# ST_LINK_V2-1.net
KiCad netlist of a schematic drawn in Altium Designer
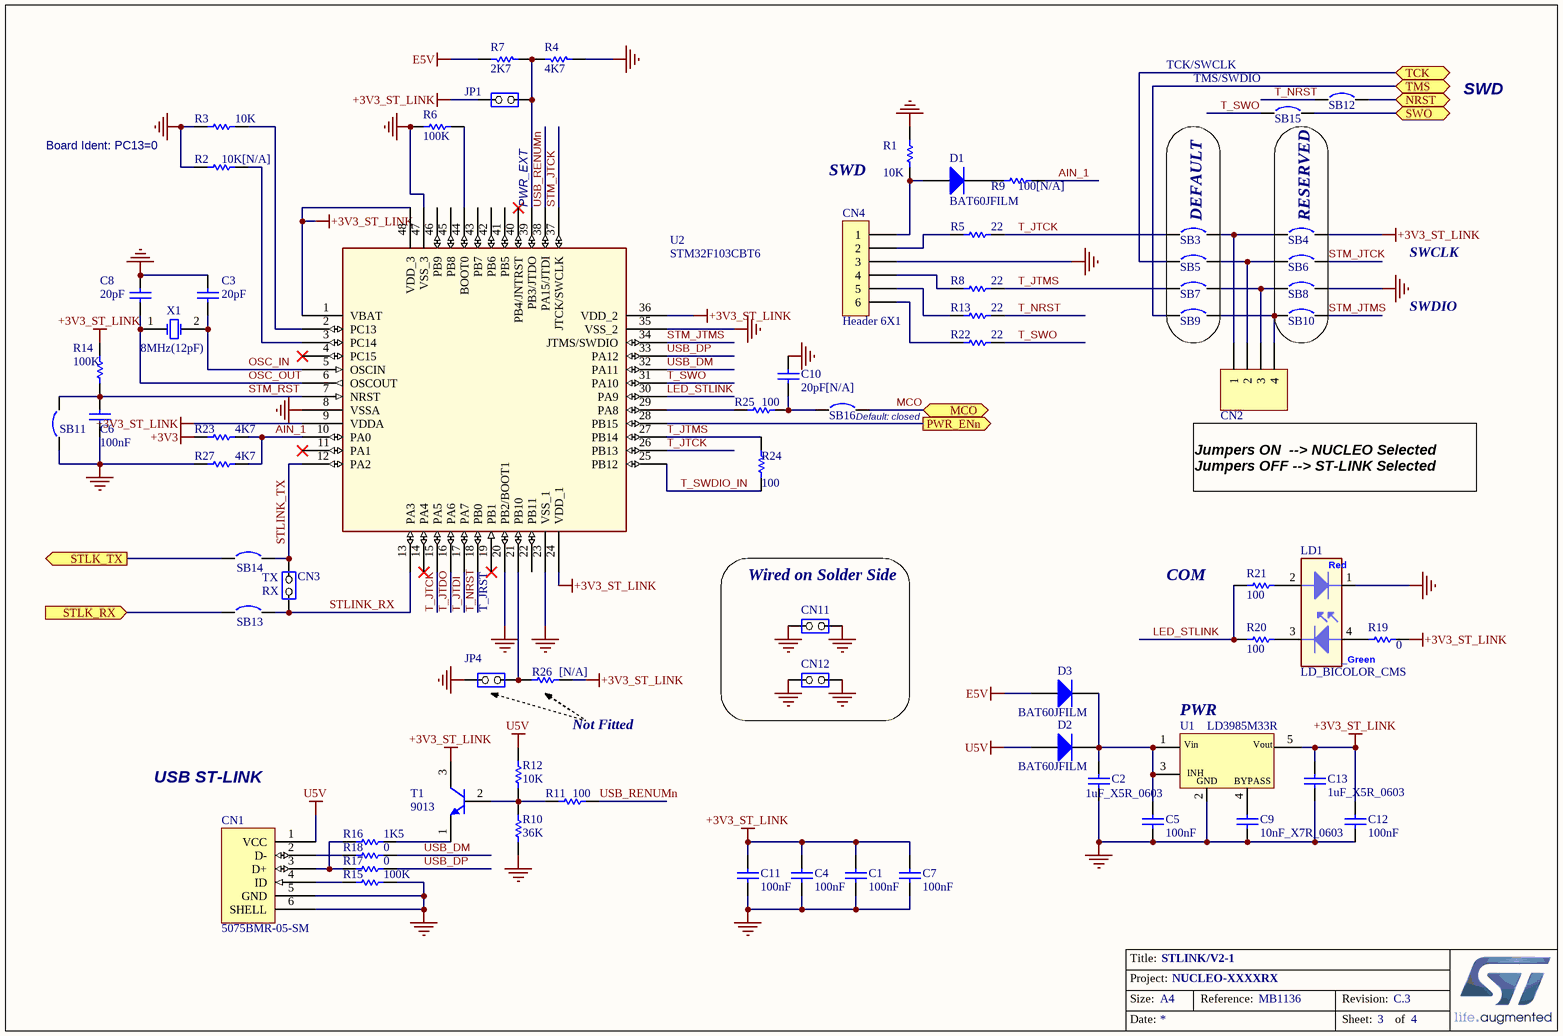
[diagram p0: ST_LINK_V2-1.SCHDOC]

(export (version "E")
  (design (tool "Eeschema 10.0.6"))
  (components
    (comp (ref "C1")
      (value "100nF")
      (footprint "0603C")
      (description "Capacitor 0402 / 0603 / 0805")
      (libsource (lib "MCD_TOOLS") (part "Capacitor_ST"))
    )
    (comp (ref "C2")
      (value "1uF_X5R_0603")
      (footprint "0603C")
      (description "0603  X5R 1µF")
      (fields (field (name "TOLERANCE") "10%"))
      (libsource (lib "MB963_1") (part "CAP SMD 0603  X5R 1µF 25V 10%"))
    )
    (comp (ref "C3")
      (value "20pF")
      (footprint "0603C")
      (description "Capacitor 0402 / 0603 / 0805")
      (libsource (lib "MCD_TOOLS") (part "Capacitor_ST"))
    )
    (comp (ref "C4")
      (value "100nF")
      (footprint "0603C")
      (description "Capacitor 0402 / 0603 / 0805")
      (libsource (lib "MCD_TOOLS") (part "Capacitor_ST"))
    )
    (comp (ref "C5")
      (value "100nF")
      (footprint "0603C")
      (description "Capacitor 0402 / 0603 / 0805")
      (libsource (lib "MCD_TOOLS") (part "Capacitor_ST"))
    )
    (comp (ref "C6")
      (value "100nF")
      (footprint "0603C")
      (description "Capacitor 0402 / 0603 / 0805")
      (libsource (lib "MCD_TOOLS") (part "Capacitor_ST"))
    )
    (comp (ref "C7")
      (value "100nF")
      (footprint "0603C")
      (description "Capacitor 0402 / 0603 / 0805")
      (libsource (lib "MCD_TOOLS") (part "Capacitor_ST"))
    )
    (comp (ref "C8")
      (value "20pF")
      (footprint "0603C")
      (description "Capacitor 0402 / 0603 / 0805")
      (libsource (lib "MCD_TOOLS") (part "Capacitor_ST"))
    )
    (comp (ref "C9")
      (value "10nF_X7R_0603")
      (footprint "0603C")
      (description "0603  X7R 10NF")
      (fields (field (name "TOLERANCE") "10%"))
      (libsource (lib "MB963_1") (part "CAP SMD 0603  X7R 10000PF 50V 10%"))
    )
    (comp (ref "C10")
      (value "20pF[N/A]")
      (footprint "0603C")
      (description "Capacitor 0402 / 0603 / 0805")
      (libsource (lib "MCD_TOOLS") (part "Capacitor_ST"))
    )
    (comp (ref "C11")
      (value "100nF")
      (footprint "0603C")
      (description "Capacitor 0402 / 0603 / 0805")
      (libsource (lib "MCD_TOOLS") (part "Capacitor_ST"))
    )
    (comp (ref "C12")
      (value "100nF")
      (footprint "0603C")
      (description "Capacitor 0402 / 0603 / 0805")
      (libsource (lib "MCD_TOOLS") (part "Capacitor_ST"))
    )
    (comp (ref "C13")
      (value "1uF_X5R_0603")
      (footprint "0603C")
      (description "0603  X5R 1µF")
      (fields (field (name "TOLERANCE") "10%"))
      (libsource (lib "MB963_1") (part "CAP SMD 0603  X5R 1µF 25V 10%"))
    )
    (comp (ref "CN1")
      (value "5075BMR-05-SM")
      (footprint "USB-MINI-B-SMD")
      (description "USB-MINI-typeB connector")
      (libsource (lib "MCD_TOOLS") (part "USB-MINI-typeB connector"))
    )
    (comp (ref "CN2")
      (value "Header 4")
      (footprint "1*4")
      (description "Header, 4-Pin, Single row")
      (fields (field (name "PUBLISHER") "Altium Limited"))
      (libsource (lib "Nucleo_64") (part "Header 4"))
    )
    (comp (ref "CN3") (value "~") (footprint "SIP2/2.54") (libsource (lib "MCD_TOOLS") (part "JP2")))
    (comp (ref "CN4")
      (value "Header 6X1")
      (footprint "1*6P")
      (description "Header, 6-Pin, Single row")
      (fields (field (name "PUBLISHER") "Altium Limited"))
      (libsource (lib "Nucleo_64") (part "Header 6X1"))
    )
    (comp (ref "CN11") (value "~") (footprint "SIP2/2.54") (libsource (lib "*") (part "JP2")))
    (comp (ref "CN12") (value "~") (footprint "SIP2/2.54") (libsource (lib "*") (part "JP2")))
    (comp (ref "D1")
      (value "BAT60JFILM")
      (footprint "SOD323/A")
      (libsource (lib "MCD_TOOLS") (part "BAT60JFILM"))
    )
    (comp (ref "D2")
      (value "BAT60JFILM")
      (footprint "SOD323/A")
      (libsource (lib "MCD_TOOLS") (part "BAT60JFILM"))
    )
    (comp (ref "D3")
      (value "BAT60JFILM")
      (footprint "SOD323/A")
      (libsource (lib "MCD_TOOLS") (part "BAT60JFILM"))
    )
    (comp (ref "JP1") (value "~") (footprint "SIP2/2.54") (libsource (lib "*") (part "JP2")))
    (comp (ref "JP4") (value "~") (footprint "SIP2/2.54") (libsource (lib "*") (part "JP2")))
    (comp (ref "LD1")
      (value "LD_BICOLOR_CMS")
      (footprint "HSMF-A201")
      (description "Bicolor Led")
      (libsource (lib "MCD_TOOLS") (part "LD_BICOLOR_CMS"))
    )
    (comp (ref "R1")
      (value "10K")
      (footprint "0603R")
      (description "Resistor 0402 or 0603 or 0805")
      (libsource (lib "Miscellaneous Devices") (part "Res1"))
    )
    (comp (ref "R2")
      (value "10K[N/A]")
      (footprint "0603R")
      (description "Resistor 0402 or 0603 or 0805")
      (libsource (lib "Miscellaneous Devices") (part "Res1"))
    )
    (comp (ref "R3")
      (value "10K")
      (footprint "0603R")
      (description "Resistor 0402 or 0603 or 0805")
      (libsource (lib "Miscellaneous Devices") (part "Res1"))
    )
    (comp (ref "R4")
      (value "4K7")
      (footprint "0603R")
      (description "Resistor")
      (fields (field (name "PUBLISHER") "Altium Limited"))
      (libsource (lib "") (part "Res1_2"))
    )
    (comp (ref "R5")
      (value "22")
      (footprint "0603R")
      (description "Resistor 0402 or 0603 or 0805")
      (libsource (lib "Miscellaneous Devices") (part "Res1"))
    )
    (comp (ref "R6")
      (value "100K")
      (footprint "0603R")
      (description "Resistor 0402 or 0603 or 0805")
      (libsource (lib "Miscellaneous Devices") (part "Res1"))
    )
    (comp (ref "R7")
      (value "2K7")
      (footprint "0603R")
      (description "Resistor")
      (fields (field (name "PUBLISHER") "Altium Limited"))
      (libsource (lib "") (part "Res1_2"))
    )
    (comp (ref "R8")
      (value "22")
      (footprint "0603R")
      (description "Resistor 0402 or 0603 or 0805")
      (libsource (lib "Miscellaneous Devices") (part "Res1"))
    )
    (comp (ref "R9")
      (value "100[N/A]")
      (footprint "0603R")
      (description "Resistor 0402 or 0603 or 0805")
      (libsource (lib "Miscellaneous Devices") (part "Res1"))
    )
    (comp (ref "R10")
      (value "36K")
      (footprint "0603R")
      (description "Resistor")
      (fields (field (name "PUBLISHER") "Altium Limited"))
      (libsource (lib "") (part "Res1_1"))
    )
    (comp (ref "R11")
      (value "100")
      (footprint "0603R")
      (description "Resistor 0402 or 0603 or 0805")
      (libsource (lib "Miscellaneous Devices") (part "Res1"))
    )
    (comp (ref "R12")
      (value "10K")
      (footprint "0603R")
      (description "Resistor")
      (fields (field (name "PUBLISHER") "Altium Limited"))
      (libsource (lib "") (part "Res1_1"))
    )
    (comp (ref "R13")
      (value "22")
      (footprint "0603R")
      (description "Resistor 0402 or 0603 or 0805")
      (libsource (lib "Miscellaneous Devices") (part "Res1"))
    )
    (comp (ref "R14")
      (value "100K")
      (footprint "0603R")
      (description "Resistor 0402 or 0603 or 0805")
      (libsource (lib "Miscellaneous Devices") (part "Res1"))
    )
    (comp (ref "R15")
      (value "100K")
      (footprint "0603R")
      (description "Resistor 0402 or 0603 or 0805")
      (libsource (lib "Miscellaneous Devices") (part "Res1"))
    )
    (comp (ref "R16")
      (value "1K5")
      (footprint "0603R")
      (description "Resistor 0402 or 0603 or 0805")
      (libsource (lib "Miscellaneous Devices") (part "Res1"))
    )
    (comp (ref "R17")
      (value "0")
      (footprint "0603R")
      (description "Resistor 0402 or 0603 or 0805")
      (libsource (lib "Miscellaneous Devices") (part "Res1"))
    )
    (comp (ref "R18")
      (value "0")
      (footprint "0603R")
      (description "Resistor 0402 or 0603 or 0805")
      (libsource (lib "Miscellaneous Devices") (part "Res1"))
    )
    (comp (ref "R19")
      (value "0")
      (footprint "0603R")
      (description "Resistor 0402 or 0603 or 0805")
      (libsource (lib "Miscellaneous Devices") (part "Res1"))
    )
    (comp (ref "R20")
      (value "100")
      (footprint "0603R")
      (description "Resistor 0402 or 0603 or 0805")
      (libsource (lib "Miscellaneous Devices") (part "Res1"))
    )
    (comp (ref "R21")
      (value "100")
      (footprint "0603R")
      (description "Resistor 0402 or 0603 or 0805")
      (libsource (lib "Miscellaneous Devices") (part "Res1"))
    )
    (comp (ref "R22")
      (value "22")
      (footprint "0603R")
      (description "Resistor 0402 or 0603 or 0805")
      (libsource (lib "Miscellaneous Devices") (part "Res1"))
    )
    (comp (ref "R23")
      (value "4K7")
      (footprint "0603R")
      (description "Resistor 0402 or 0603 or 0805")
      (libsource (lib "Miscellaneous Devices") (part "Res1"))
    )
    (comp (ref "R24")
      (value "100")
      (footprint "0603R")
      (description "Resistor 0402 or 0603 or 0805")
      (libsource (lib "Miscellaneous Devices") (part "Res1"))
    )
    (comp (ref "R25")
      (value "100")
      (footprint "0603R")
      (description "Resistor 0402 or 0603 or 0805")
      (libsource (lib "Miscellaneous Devices") (part "Res1"))
    )
    (comp (ref "R26")
      (value "[N/A]")
      (footprint "0603R")
      (description "Resistor")
      (fields (field (name "PUBLISHER") "Altium Limited"))
      (libsource (lib "") (part "Res1_1"))
    )
    (comp (ref "R27")
      (value "4K7")
      (footprint "0603R")
      (description "Resistor 0402 or 0603 or 0805")
      (libsource (lib "Miscellaneous Devices") (part "Res1"))
    )
    (comp (ref "SB3")
      (value "Circuit Breaker")
      (footprint "JP2_SMD")
      (fields (field (name "PUBLISHER") "Altium Limited"))
      (libsource (lib "MB915") (part "Circuit Breaker"))
    )
    (comp (ref "SB4")
      (value "Circuit Breaker")
      (footprint "JP2_SMD")
      (fields (field (name "PUBLISHER") "Altium Limited"))
      (libsource (lib "MB915") (part "Circuit Breaker"))
    )
    (comp (ref "SB5")
      (value "Circuit Breaker")
      (footprint "JP2_SMD")
      (fields (field (name "PUBLISHER") "Altium Limited"))
      (libsource (lib "MB915") (part "Circuit Breaker"))
    )
    (comp (ref "SB6")
      (value "Circuit Breaker")
      (footprint "JP2_SMD")
      (fields (field (name "PUBLISHER") "Altium Limited"))
      (libsource (lib "MB915") (part "Circuit Breaker"))
    )
    (comp (ref "SB7")
      (value "Circuit Breaker")
      (footprint "JP2_SMD")
      (fields (field (name "PUBLISHER") "Altium Limited"))
      (libsource (lib "MB915") (part "Circuit Breaker"))
    )
    (comp (ref "SB8")
      (value "Circuit Breaker")
      (footprint "JP2_SMD")
      (fields (field (name "PUBLISHER") "Altium Limited"))
      (libsource (lib "MB915") (part "Circuit Breaker"))
    )
    (comp (ref "SB9")
      (value "Circuit Breaker")
      (footprint "JP2_SMD")
      (fields (field (name "PUBLISHER") "Altium Limited"))
      (libsource (lib "MB915") (part "Circuit Breaker"))
    )
    (comp (ref "SB10")
      (value "Circuit Breaker")
      (footprint "JP2_SMD")
      (fields (field (name "PUBLISHER") "Altium Limited"))
      (libsource (lib "MB915") (part "Circuit Breaker"))
    )
    (comp (ref "SB11")
      (value "Circuit Breaker")
      (footprint "JP2_SMD")
      (fields (field (name "PUBLISHER") "Altium Limited"))
      (libsource (lib "MB915") (part "Circuit Breaker"))
    )
    (comp (ref "SB12")
      (value "Circuit Breaker")
      (footprint "JP2_SMD")
      (fields (field (name "PUBLISHER") "Altium Limited"))
      (libsource (lib "MB915") (part "Circuit Breaker"))
    )
    (comp (ref "SB13")
      (value "Circuit Breaker")
      (footprint "JP2_SMD")
      (fields (field (name "PUBLISHER") "Altium Limited"))
      (libsource (lib "MCD_TOOLS") (part "Circuit Breaker"))
    )
    (comp (ref "SB14")
      (value "Circuit Breaker")
      (footprint "JP2_SMD")
      (fields (field (name "PUBLISHER") "Altium Limited"))
      (libsource (lib "MCD_TOOLS") (part "Circuit Breaker"))
    )
    (comp (ref "SB15")
      (value "Circuit Breaker")
      (footprint "JP2_SMD")
      (fields (field (name "PUBLISHER") "Altium Limited"))
      (libsource (lib "MCD_TOOLS") (part "Circuit Breaker"))
    )
    (comp (ref "SB16")
      (value "Circuit Breaker")
      (footprint "JP2_SMD")
      (fields (field (name "PUBLISHER") "Altium Limited"))
      (libsource (lib "MCD_TOOLS") (part "Circuit Breaker"))
    )
    (comp (ref "T1")
      (value "9013")
      (footprint "SOT-23")
      (description "NPN Bipolar Transistor")
      (fields (field (name "PUBLISHER") "Altium Limited"))
      (libsource (lib "Miscellaneous Devices") (part "NPN"))
    )
    (comp (ref "U1")
      (value "LD3985M33R")
      (footprint "SOT-23-5L")
      (description "Ultra low drop-low noise BiCMOS voltage, regulators low ESR capacitors compatible")
      (libsource (lib "MCD_TOOLS") (part "LD3985M33R"))
    )
    (comp (ref "U2")
      (value "STM32F103CBT6")
      (footprint "QFP48 7X7")
      (description "Medium-density performance line ARM-based 32-bit MCU with 64KB Flash")
      (libsource (lib "Nucleo_64") (part "STM32F103CBT6"))
    )
    (comp (ref "X1")
      (value "8MHz(12pF)")
      (footprint "XTAL1")
      (description "Crystal Oscillator")
      (fields (field (name "PUBLISHER") "Altium Limited"))
      (libsource (lib "MB963_1") (part "XTAL"))
    )
  )
  (nets
    (net (code "1") (name "+3V3") (class "Default")
      (node (ref "R23") (pin "1") (pinfunction "1_1") (pintype "passive"))
    )
    (net (code "2") (name "+3V3_ST_LINK") (class "Default")
      (node (ref "C1") (pin "2") (pinfunction "2_2") (pintype "passive"))
      (node (ref "C11") (pin "2") (pinfunction "2_2") (pintype "passive"))
      (node (ref "C12") (pin "2") (pinfunction "2_2") (pintype "passive"))
      (node (ref "C13") (pin "1") (pinfunction "1_1") (pintype "passive"))
      (node (ref "C4") (pin "2") (pinfunction "2_2") (pintype "passive"))
      (node (ref "C7") (pin "2") (pinfunction "2_2") (pintype "passive"))
      (node (ref "JP1") (pin "1") (pinfunction "COMMON_1") (pintype "passive"))
      (node (ref "R14") (pin "2") (pinfunction "2_2") (pintype "passive"))
      (node (ref "R19") (pin "2") (pinfunction "2_2") (pintype "passive"))
      (node (ref "R26") (pin "1") (pinfunction "1_1") (pintype "passive"))
      (node (ref "SB4") (pin "2") (pinfunction "2_2") (pintype "passive"))
      (node (ref "T1") (pin "3") (pinfunction "C_3") (pintype "passive"))
      (node (ref "U1") (pin "5") (pinfunction "Vout_5") (pintype "passive"))
      (node (ref "U2") (pin "1") (pinfunction "VBAT_1") (pintype "power_in"))
      (node (ref "U2") (pin "24") (pinfunction "VDD_1_24") (pintype "power_in"))
      (node (ref "U2") (pin "36") (pinfunction "VDD_2_36") (pintype "power_in"))
      (node (ref "U2") (pin "48") (pinfunction "VDD_3_48") (pintype "power_in"))
      (node (ref "U2") (pin "9") (pinfunction "VDDA_9") (pintype "power_in"))
    )
    (net (code "3") (name "/AIN_1") (class "Default")
      (node (ref "R23") (pin "2") (pinfunction "2_2") (pintype "passive"))
      (node (ref "R27") (pin "2") (pinfunction "2_2") (pintype "passive"))
      (node (ref "R9") (pin "2") (pinfunction "2_2") (pintype "passive"))
      (node (ref "U2") (pin "10") (pinfunction "PA0_10") (pintype "bidirectional"))
    )
    (net (code "4") (name "/LED_STLINK") (class "Default")
      (node (ref "R20") (pin "1") (pinfunction "1_1") (pintype "passive"))
      (node (ref "R21") (pin "1") (pinfunction "1_1") (pintype "passive"))
      (node (ref "U2") (pin "30") (pinfunction "PA9_30") (pintype "bidirectional"))
    )
    (net (code "5") (name "/MCO") (class "Default")
      (node (ref "SB16") (pin "2") (pinfunction "2_2") (pintype "passive"))
    )
    (net (code "6") (name "/NRST") (class "Default")
      (node (ref "SB12") (pin "2") (pinfunction "2_2") (pintype "passive"))
    )
    (net (code "7") (name "/OSC_IN") (class "Default")
      (node (ref "C3") (pin "1") (pinfunction "1_1") (pintype "passive"))
      (node (ref "U2") (pin "5") (pinfunction "OSCIN_5") (pintype "input"))
      (node (ref "X1") (pin "2") (pinfunction "OSC2_2") (pintype "passive"))
    )
    (net (code "8") (name "/OSC_OUT") (class "Default")
      (node (ref "C8") (pin "1") (pinfunction "1_1") (pintype "passive"))
      (node (ref "U2") (pin "6") (pinfunction "OSCOUT_6") (pintype "output"))
      (node (ref "X1") (pin "1") (pinfunction "OSC1_1") (pintype "passive"))
    )
    (net (code "9") (name "/PWR_ENn") (class "Default")
      (node (ref "U2") (pin "28") (pinfunction "PB15_28") (pintype "bidirectional"))
    )
    (net (code "10") (name "/STLINK_RX") (class "Default")
      (node (ref "CN3") (pin "1") (pinfunction "COMMON_1") (pintype "passive"))
      (node (ref "SB13") (pin "2") (pinfunction "2_2") (pintype "passive"))
      (node (ref "U2") (pin "13") (pinfunction "PA3_13") (pintype "bidirectional"))
    )
    (net (code "11") (name "/STLINK_TX") (class "Default")
      (node (ref "CN3") (pin "2") (pinfunction "NO_2") (pintype "passive"))
      (node (ref "SB14") (pin "2") (pinfunction "2_2") (pintype "passive"))
      (node (ref "U2") (pin "12") (pinfunction "PA2_12") (pintype "bidirectional"))
    )
    (net (code "12") (name "/STLK_RX") (class "Default")
      (node (ref "SB13") (pin "1") (pinfunction "1_1") (pintype "passive"))
    )
    (net (code "13") (name "/STLK_TX") (class "Default")
      (node (ref "SB14") (pin "1") (pinfunction "1_1") (pintype "passive"))
    )
    (net (code "14") (name "/STM_JTCK") (class "Default")
      (node (ref "SB6") (pin "2") (pinfunction "2_2") (pintype "passive"))
      (node (ref "U2") (pin "37") (pinfunction "JTCK/SWCLK_37") (pintype "bidirectional"))
    )
    (net (code "15") (name "/STM_JTMS") (class "Default")
      (node (ref "SB10") (pin "2") (pinfunction "2_2") (pintype "passive"))
      (node (ref "U2") (pin "34") (pinfunction "JTMS/SWDIO_34") (pintype "bidirectional"))
    )
    (net (code "16") (name "/STM_RST") (class "Default")
      (node (ref "C6") (pin "2") (pinfunction "2_2") (pintype "passive"))
      (node (ref "R14") (pin "1") (pinfunction "1_1") (pintype "passive"))
      (node (ref "SB11") (pin "2") (pinfunction "2_2") (pintype "passive"))
      (node (ref "U2") (pin "7") (pinfunction "NRST_7") (pintype "input"))
    )
    (net (code "17") (name "/SWO") (class "Default")
      (node (ref "SB15") (pin "2") (pinfunction "2_2") (pintype "passive"))
    )
    (net (code "18") (name "/TCK") (class "Default")
      (node (ref "SB5") (pin "1") (pinfunction "1_1") (pintype "passive"))
    )
    (net (code "19") (name "/TMS") (class "Default")
      (node (ref "SB9") (pin "1") (pinfunction "1_1") (pintype "passive"))
    )
    (net (code "20") (name "/T_JTCK") (class "Default")
      (node (ref "R5") (pin "2") (pinfunction "2_2") (pintype "passive"))
      (node (ref "SB3") (pin "1") (pinfunction "1_1") (pintype "passive"))
      (node (ref "U2") (pin "15") (pinfunction "PA5_15") (pintype "bidirectional"))
      (node (ref "U2") (pin "26") (pinfunction "PB13_26") (pintype "bidirectional"))
    )
    (net (code "21") (name "/T_JTDI") (class "Default")
      (node (ref "U2") (pin "17") (pinfunction "PA7_17") (pintype "bidirectional"))
    )
    (net (code "22") (name "/T_JTDO") (class "Default")
      (node (ref "U2") (pin "16") (pinfunction "PA6_16") (pintype "bidirectional"))
    )
    (net (code "23") (name "/T_JTMS") (class "Default")
      (node (ref "R24") (pin "2") (pinfunction "2_2") (pintype "passive"))
      (node (ref "R8") (pin "2") (pinfunction "2_2") (pintype "passive"))
      (node (ref "SB7") (pin "1") (pinfunction "1_1") (pintype "passive"))
      (node (ref "U2") (pin "27") (pinfunction "PB14_27") (pintype "bidirectional"))
    )
    (net (code "24") (name "/T_NRST") (class "Default")
      (node (ref "R13") (pin "2") (pinfunction "2_2") (pintype "passive"))
      (node (ref "SB12") (pin "1") (pinfunction "1_1") (pintype "passive"))
      (node (ref "U2") (pin "18") (pinfunction "PB0_18") (pintype "bidirectional"))
    )
    (net (code "25") (name "/T_SWDIO_IN") (class "Default")
      (node (ref "R24") (pin "1") (pinfunction "1_1") (pintype "passive"))
      (node (ref "U2") (pin "25") (pinfunction "PB12_25") (pintype "bidirectional"))
    )
    (net (code "26") (name "/T_SWO") (class "Default")
      (node (ref "R22") (pin "2") (pinfunction "2_2") (pintype "passive"))
      (node (ref "SB15") (pin "1") (pinfunction "1_1") (pintype "passive"))
      (node (ref "U2") (pin "31") (pinfunction "PA10_31") (pintype "bidirectional"))
    )
    (net (code "27") (name "/USB_DM") (class "Default")
      (node (ref "R18") (pin "2") (pinfunction "2_2") (pintype "passive"))
      (node (ref "U2") (pin "32") (pinfunction "PA11_32") (pintype "bidirectional"))
    )
    (net (code "28") (name "/USB_DP") (class "Default")
      (node (ref "R17") (pin "2") (pinfunction "2_2") (pintype "passive"))
      (node (ref "U2") (pin "33") (pinfunction "PA12_33") (pintype "bidirectional"))
    )
    (net (code "29") (name "/USB_RENUMn") (class "Default")
      (node (ref "R11") (pin "2") (pinfunction "2_2") (pintype "passive"))
      (node (ref "U2") (pin "38") (pinfunction "PA15/JTDI_38") (pintype "bidirectional"))
    )
    (net (code "30") (name "E5V") (class "Default")
      (node (ref "D3") (pin "1") (pinfunction "A_1") (pintype "passive"))
      (node (ref "R7") (pin "1") (pinfunction "1_1") (pintype "passive"))
    )
    (net (code "31") (name "GND") (class "Default")
      (node (ref "C1") (pin "1") (pinfunction "1_1") (pintype "passive"))
      (node (ref "C10") (pin "2") (pinfunction "2_2") (pintype "passive"))
      (node (ref "C11") (pin "1") (pinfunction "1_1") (pintype "passive"))
      (node (ref "C12") (pin "1") (pinfunction "1_1") (pintype "passive"))
      (node (ref "C13") (pin "2") (pinfunction "2_2") (pintype "passive"))
      (node (ref "C2") (pin "1") (pinfunction "1_1") (pintype "passive"))
      (node (ref "C3") (pin "2") (pinfunction "2_2") (pintype "passive"))
      (node (ref "C4") (pin "1") (pinfunction "1_1") (pintype "passive"))
      (node (ref "C5") (pin "1") (pinfunction "1_1") (pintype "passive"))
      (node (ref "C6") (pin "1") (pinfunction "1_1") (pintype "passive"))
      (node (ref "C7") (pin "1") (pinfunction "1_1") (pintype "passive"))
      (node (ref "C8") (pin "2") (pinfunction "2_2") (pintype "passive"))
      (node (ref "C9") (pin "1") (pinfunction "1_1") (pintype "passive"))
      (node (ref "CN1") (pin "5") (pinfunction "GND_5") (pintype "power_in"))
      (node (ref "CN1") (pin "6") (pinfunction "SHELL_6") (pintype "power_in"))
      (node (ref "CN11") (pin "1") (pinfunction "COMMON_1") (pintype "passive"))
      (node (ref "CN11") (pin "2") (pinfunction "NO_2") (pintype "passive"))
      (node (ref "CN12") (pin "1") (pinfunction "COMMON_1") (pintype "passive"))
      (node (ref "CN12") (pin "2") (pinfunction "NO_2") (pintype "passive"))
      (node (ref "CN4") (pin "3") (pinfunction "3_3") (pintype "passive"))
      (node (ref "JP4") (pin "1") (pinfunction "COMMON_1") (pintype "passive"))
      (node (ref "LD1") (pin "1") (pinfunction "1_1") (pintype "passive"))
      (node (ref "R1") (pin "2") (pinfunction "2_2") (pintype "passive"))
      (node (ref "R10") (pin "1") (pinfunction "1_1") (pintype "passive"))
      (node (ref "R15") (pin "2") (pinfunction "2_2") (pintype "passive"))
      (node (ref "R2") (pin "1") (pinfunction "1_1") (pintype "passive"))
      (node (ref "R27") (pin "1") (pinfunction "1_1") (pintype "passive"))
      (node (ref "R3") (pin "1") (pinfunction "1_1") (pintype "passive"))
      (node (ref "R4") (pin "2") (pinfunction "2_2") (pintype "passive"))
      (node (ref "R6") (pin "1") (pinfunction "1_1") (pintype "passive"))
      (node (ref "SB11") (pin "1") (pinfunction "1_1") (pintype "passive"))
      (node (ref "SB8") (pin "2") (pinfunction "2_2") (pintype "passive"))
      (node (ref "U1") (pin "2") (pinfunction "GND_2") (pintype "passive"))
      (node (ref "U2") (pin "20") (pinfunction "PB2/BOOT1_20") (pintype "bidirectional"))
      (node (ref "U2") (pin "23") (pinfunction "VSS_1_23") (pintype "power_in"))
      (node (ref "U2") (pin "35") (pinfunction "VSS_2_35") (pintype "power_in"))
      (node (ref "U2") (pin "47") (pinfunction "VSS_3_47") (pintype "power_in"))
      (node (ref "U2") (pin "8") (pinfunction "VSSA_8") (pintype "power_in"))
    )
    (net (code "32") (name "Net-(C10-Pad1)") (class "Default")
      (node (ref "C10") (pin "1") (pinfunction "1_1") (pintype "passive"))
      (node (ref "R25") (pin "2") (pinfunction "2_2") (pintype "passive"))
      (node (ref "SB16") (pin "1") (pinfunction "1_1") (pintype "passive"))
    )
    (net (code "33") (name "Net-(CN1-D+)") (class "Default")
      (node (ref "CN1") (pin "3") (pinfunction "D+_3") (pintype "bidirectional"))
      (node (ref "R16") (pin "1") (pinfunction "1_1") (pintype "passive"))
      (node (ref "R17") (pin "1") (pinfunction "1_1") (pintype "passive"))
    )
    (net (code "34") (name "Net-(CN1-D-)") (class "Default")
      (node (ref "CN1") (pin "2") (pinfunction "D-_2") (pintype "bidirectional"))
      (node (ref "R18") (pin "1") (pinfunction "1_1") (pintype "passive"))
    )
    (net (code "35") (name "Net-(CN1-ID)") (class "Default")
      (node (ref "CN1") (pin "4") (pinfunction "ID_4") (pintype "input"))
      (node (ref "R15") (pin "1") (pinfunction "1_1") (pintype "passive"))
    )
    (net (code "36") (name "Net-(CN2-Pad1)") (class "Default")
      (node (ref "CN2") (pin "1") (pinfunction "1_1") (pintype "passive"))
      (node (ref "SB3") (pin "2") (pinfunction "2_2") (pintype "passive"))
      (node (ref "SB4") (pin "1") (pinfunction "1_1") (pintype "passive"))
    )
    (net (code "37") (name "Net-(CN2-Pad2)") (class "Default")
      (node (ref "CN2") (pin "2") (pinfunction "2_2") (pintype "passive"))
      (node (ref "SB5") (pin "2") (pinfunction "2_2") (pintype "passive"))
      (node (ref "SB6") (pin "1") (pinfunction "1_1") (pintype "passive"))
    )
    (net (code "38") (name "Net-(CN2-Pad3)") (class "Default")
      (node (ref "CN2") (pin "3") (pinfunction "3_3") (pintype "passive"))
      (node (ref "SB7") (pin "2") (pinfunction "2_2") (pintype "passive"))
      (node (ref "SB8") (pin "1") (pinfunction "1_1") (pintype "passive"))
    )
    (net (code "39") (name "Net-(CN2-Pad4)") (class "Default")
      (node (ref "CN2") (pin "4") (pinfunction "4_4") (pintype "passive"))
      (node (ref "SB10") (pin "1") (pinfunction "1_1") (pintype "passive"))
      (node (ref "SB9") (pin "2") (pinfunction "2_2") (pintype "passive"))
    )
    (net (code "40") (name "Net-(CN4-Pad2)") (class "Default")
      (node (ref "CN4") (pin "2") (pinfunction "2_2") (pintype "passive"))
      (node (ref "R5") (pin "1") (pinfunction "1_1") (pintype "passive"))
    )
    (net (code "41") (name "Net-(CN4-Pad4)") (class "Default")
      (node (ref "CN4") (pin "4") (pinfunction "4_4") (pintype "passive"))
      (node (ref "R8") (pin "1") (pinfunction "1_1") (pintype "passive"))
    )
    (net (code "42") (name "Net-(CN4-Pad5)") (class "Default")
      (node (ref "CN4") (pin "5") (pinfunction "5_5") (pintype "passive"))
      (node (ref "R13") (pin "1") (pinfunction "1_1") (pintype "passive"))
    )
    (net (code "43") (name "Net-(CN4-Pad6)") (class "Default")
      (node (ref "CN4") (pin "6") (pinfunction "6_6") (pintype "passive"))
      (node (ref "R22") (pin "1") (pinfunction "1_1") (pintype "passive"))
    )
    (net (code "44") (name "Net-(D1-A)") (class "Default")
      (node (ref "CN4") (pin "1") (pinfunction "1_1") (pintype "passive"))
      (node (ref "D1") (pin "1") (pinfunction "A_1") (pintype "passive"))
      (node (ref "R1") (pin "1") (pinfunction "1_1") (pintype "passive"))
    )
    (net (code "45") (name "Net-(D1-K)") (class "Default")
      (node (ref "D1") (pin "2") (pinfunction "K_2") (pintype "passive"))
      (node (ref "R9") (pin "1") (pinfunction "1_1") (pintype "passive"))
    )
    (net (code "46") (name "Net-(D2-K)") (class "Default")
      (node (ref "C2") (pin "2") (pinfunction "2_2") (pintype "passive"))
      (node (ref "C5") (pin "2") (pinfunction "2_2") (pintype "passive"))
      (node (ref "D2") (pin "2") (pinfunction "K_2") (pintype "passive"))
      (node (ref "D3") (pin "2") (pinfunction "K_2") (pintype "passive"))
      (node (ref "U1") (pin "1") (pinfunction "Vin_1") (pintype "passive"))
      (node (ref "U1") (pin "3") (pinfunction "CE_3") (pintype "passive"))
    )
    (net (code "47") (name "Net-(JP1-NO)") (class "Default")
      (node (ref "JP1") (pin "2") (pinfunction "NO_2") (pintype "passive"))
      (node (ref "R4") (pin "1") (pinfunction "1_1") (pintype "passive"))
      (node (ref "R7") (pin "2") (pinfunction "2_2") (pintype "passive"))
      (node (ref "U2") (pin "39") (pinfunction "PB3/JTDO_39") (pintype "bidirectional"))
    )
    (net (code "48") (name "Net-(JP4-NO)") (class "Default")
      (node (ref "JP4") (pin "2") (pinfunction "NO_2") (pintype "passive"))
      (node (ref "R26") (pin "2") (pinfunction "2_2") (pintype "passive"))
      (node (ref "U2") (pin "21") (pinfunction "PB10_21") (pintype "bidirectional"))
    )
    (net (code "49") (name "Net-(LD1-Pad2)") (class "Default")
      (node (ref "LD1") (pin "2") (pinfunction "2_2") (pintype "passive"))
      (node (ref "R21") (pin "2") (pinfunction "2_2") (pintype "passive"))
    )
    (net (code "50") (name "Net-(LD1-Pad3)") (class "Default")
      (node (ref "LD1") (pin "3") (pinfunction "3_3") (pintype "passive"))
      (node (ref "R20") (pin "2") (pinfunction "2_2") (pintype "passive"))
    )
    (net (code "51") (name "Net-(LD1-Pad4)") (class "Default")
      (node (ref "LD1") (pin "4") (pinfunction "4_4") (pintype "passive"))
      (node (ref "R19") (pin "1") (pinfunction "1_1") (pintype "passive"))
    )
    (net (code "52") (name "Net-(T1-B)") (class "Default")
      (node (ref "R10") (pin "2") (pinfunction "2_2") (pintype "passive"))
      (node (ref "R11") (pin "1") (pinfunction "1_1") (pintype "passive"))
      (node (ref "R12") (pin "1") (pinfunction "1_1") (pintype "passive"))
      (node (ref "T1") (pin "2") (pinfunction "B_2") (pintype "passive"))
    )
    (net (code "53") (name "Net-(T1-E)") (class "Default")
      (node (ref "R16") (pin "2") (pinfunction "2_2") (pintype "passive"))
      (node (ref "T1") (pin "1") (pinfunction "E_1") (pintype "passive"))
    )
    (net (code "54") (name "Net-(U1-BYPASS)") (class "Default")
      (node (ref "C9") (pin "2") (pinfunction "2_2") (pintype "passive"))
      (node (ref "U1") (pin "4") (pinfunction "BYPASS_4") (pintype "passive"))
    )
    (net (code "55") (name "Net-(U2-BOOT0)") (class "Default")
      (node (ref "R6") (pin "2") (pinfunction "2_2") (pintype "passive"))
      (node (ref "U2") (pin "44") (pinfunction "BOOT0_44") (pintype "bidirectional"))
    )
    (net (code "56") (name "Net-(U2-PA8)") (class "Default")
      (node (ref "R25") (pin "1") (pinfunction "1_1") (pintype "passive"))
      (node (ref "U2") (pin "29") (pinfunction "PA8_29") (pintype "bidirectional"))
    )
    (net (code "57") (name "Net-(U2-PC13)") (class "Default")
      (node (ref "R3") (pin "2") (pinfunction "2_2") (pintype "passive"))
      (node (ref "U2") (pin "2") (pinfunction "PC13_2") (pintype "bidirectional"))
    )
    (net (code "58") (name "Net-(U2-PC14)") (class "Default")
      (node (ref "R2") (pin "2") (pinfunction "2_2") (pintype "passive"))
      (node (ref "U2") (pin "3") (pinfunction "PC14_3") (pintype "bidirectional"))
    )
    (net (code "59") (name "U5V") (class "Default")
      (node (ref "CN1") (pin "1") (pinfunction "VCC_1") (pintype "power_in"))
      (node (ref "D2") (pin "1") (pinfunction "A_1") (pintype "passive"))
      (node (ref "R12") (pin "2") (pinfunction "2_2") (pintype "passive"))
    )
    (net (code "60") (name "unconnected-(U2-PA1-Pad11)") (class "Default")
      (node (ref "U2") (pin "11") (pinfunction "PA1_11") (pintype "bidirectional+no_connect"))
    )
    (net (code "61") (name "unconnected-(U2-PA4-Pad14)") (class "Default")
      (node (ref "U2") (pin "14") (pinfunction "PA4_14") (pintype "bidirectional+no_connect"))
    )
    (net (code "62") (name "unconnected-(U2-PB1-Pad19)") (class "Default")
      (node (ref "U2") (pin "19") (pinfunction "PB1_19") (pintype "input+no_connect"))
    )
    (net (code "63") (name "unconnected-(U2-PB4{slash}JNTRST-Pad40)") (class "Default")
      (node (ref "U2") (pin "40") (pinfunction "PB4/JNTRST_40") (pintype "bidirectional+no_connect"))
    )
    (net (code "64") (name "unconnected-(U2-PB5-Pad41)") (class "Default")
      (node (ref "U2") (pin "41") (pinfunction "PB5_41") (pintype "bidirectional"))
    )
    (net (code "65") (name "unconnected-(U2-PB6-Pad42)") (class "Default")
      (node (ref "U2") (pin "42") (pinfunction "PB6_42") (pintype "bidirectional"))
    )
    (net (code "66") (name "unconnected-(U2-PB7-Pad43)") (class "Default")
      (node (ref "U2") (pin "43") (pinfunction "PB7_43") (pintype "bidirectional"))
    )
    (net (code "67") (name "unconnected-(U2-PB8-Pad45)") (class "Default")
      (node (ref "U2") (pin "45") (pinfunction "PB8_45") (pintype "bidirectional"))
    )
    (net (code "68") (name "unconnected-(U2-PB9-Pad46)") (class "Default")
      (node (ref "U2") (pin "46") (pinfunction "PB9_46") (pintype "bidirectional"))
    )
    (net (code "69") (name "unconnected-(U2-PB11-Pad22)") (class "Default")
      (node (ref "U2") (pin "22") (pinfunction "PB11_22") (pintype "bidirectional"))
    )
    (net (code "70") (name "unconnected-(U2-PC15-Pad4)") (class "Default")
      (node (ref "U2") (pin "4") (pinfunction "PC15_4") (pintype "bidirectional+no_connect"))
    )
  )
)
